# Qwiic_Hall_Effect_Sensor_TMAG5273_Mini.net
KiCad netlist of a schematic drawn in EAGLE
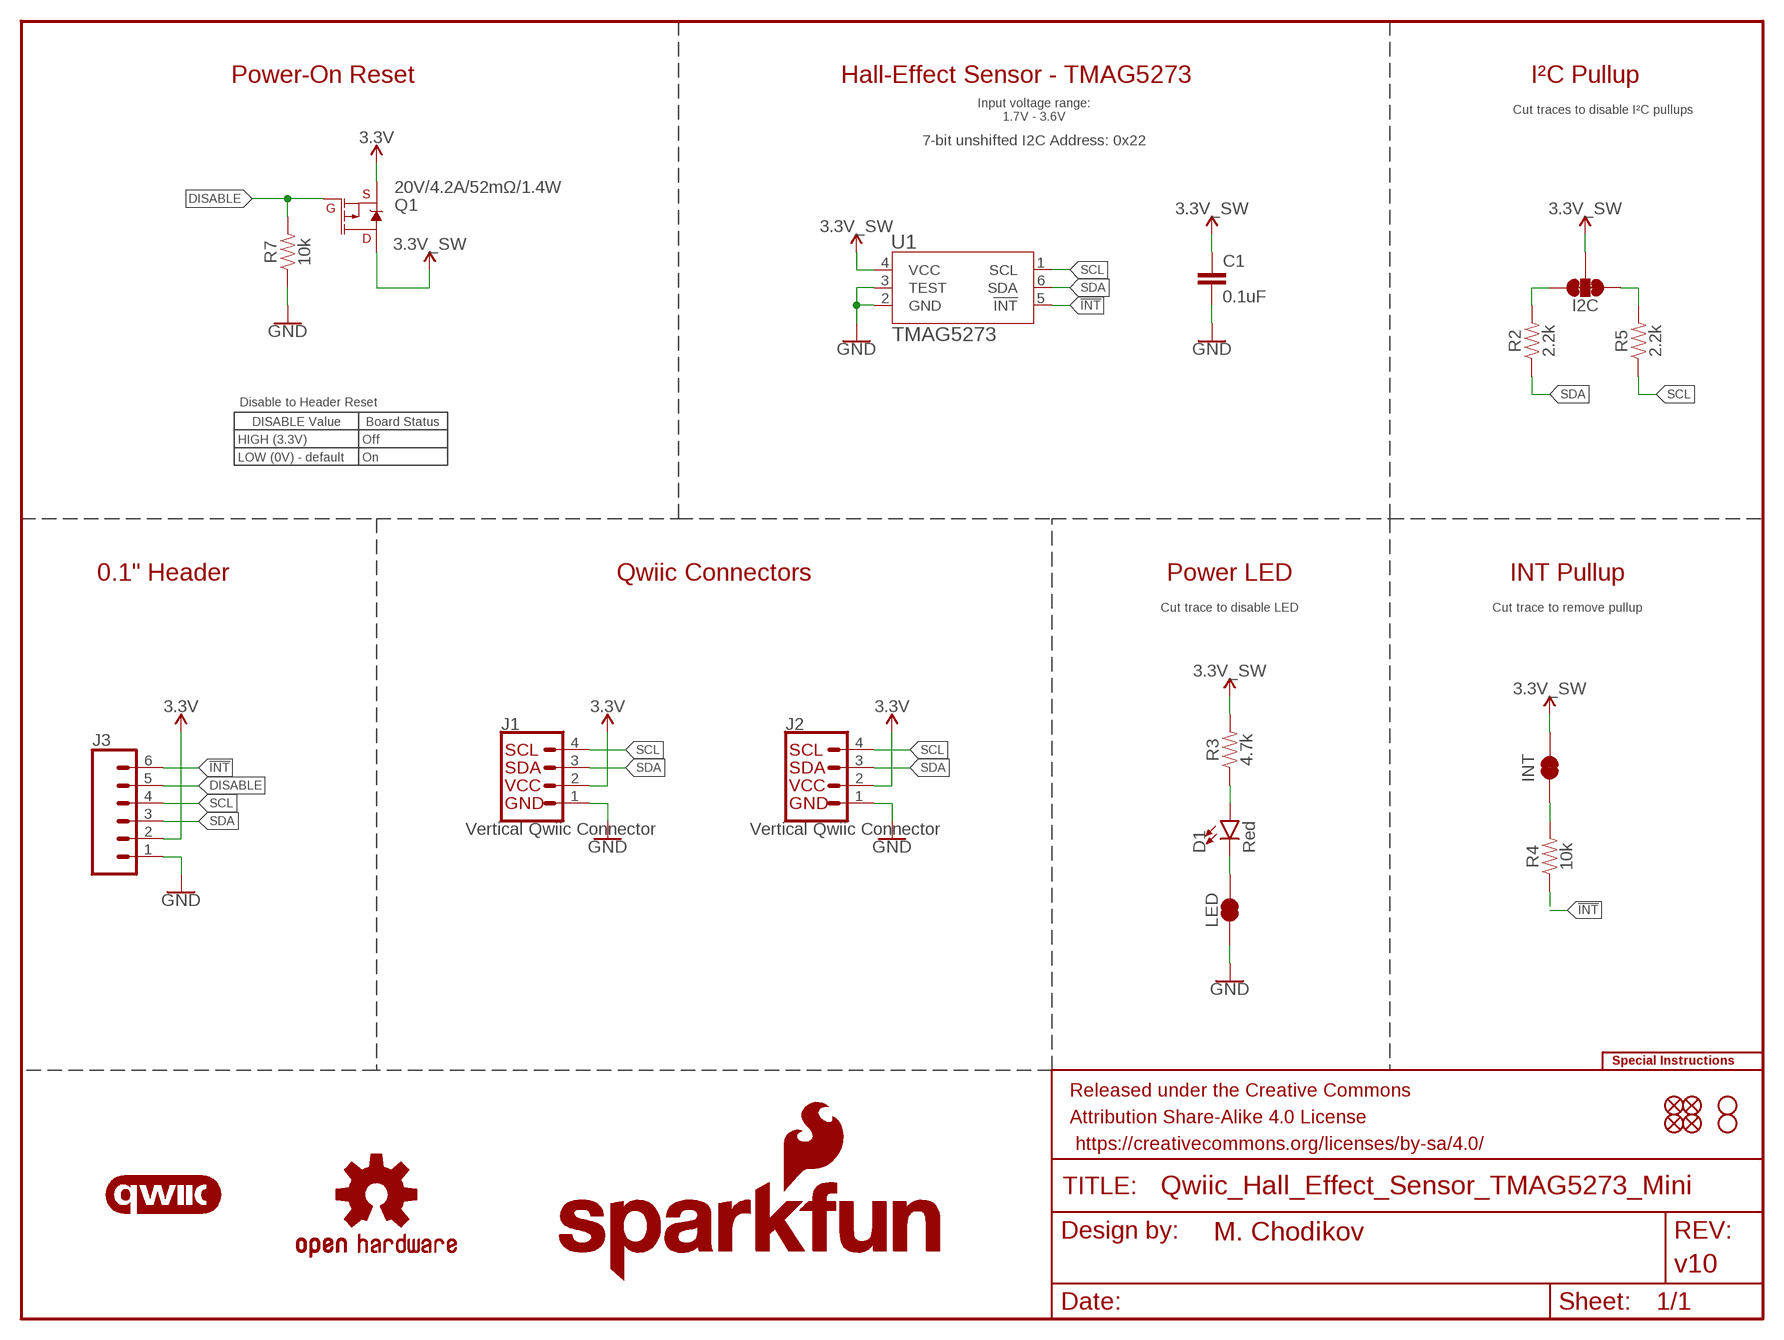
[diagram p0: schematic, sheet 1]

(export (version "E")
  (design (tool "Eeschema 10.0.6"))
  (components
    (comp (ref "C1")
      (value "0.1uF")
      (footprint "eagle-import:0603")
      (libsource (lib "eagle-import") (part "0.1UF-0603-25V-10%-X7R-WE"))
    )
    (comp (ref "D1")
      (value "Red")
      (footprint "eagle-import:LED-0603")
      (libsource (lib "eagle-import") (part "LED-RED_0603-KB"))
    )
    (comp (ref "FD1")
      (value "FIDUCIAL1X2")
      (footprint "eagle-import:FIDUCIAL-1X2")
      (libsource (lib "eagle-import") (part "FIDUCIAL1X2"))
    )
    (comp (ref "FD2")
      (value "FIDUCIAL1X2")
      (footprint "eagle-import:FIDUCIAL-1X2")
      (libsource (lib "eagle-import") (part "FIDUCIAL1X2"))
    )
    (comp (ref "FD3")
      (value "FIDUCIAL1X2")
      (footprint "eagle-import:FIDUCIAL-1X2")
      (libsource (lib "eagle-import") (part "FIDUCIAL1X2"))
    )
    (comp (ref "FD4")
      (value "FIDUCIAL1X2")
      (footprint "eagle-import:FIDUCIAL-1X2")
      (libsource (lib "eagle-import") (part "FIDUCIAL1X2"))
    )
    (comp (ref "FRAME1")
      (value "FRAME-LETTER")
      (footprint "eagle-import:CREATIVE_COMMONS")
      (fields (field (name "DESIGNER") "M. Chodikov") (field (name "REV") "v10"))
      (libsource (lib "eagle-import") (part "FRAME-LETTER"))
    )
    (comp (ref "H2")
      (value "STAND-OFF")
      (footprint "eagle-import:STAND-OFF")
      (libsource (lib "eagle-import") (part "STAND-OFF"))
    )
    (comp (ref "H4")
      (value "STAND-OFF")
      (footprint "eagle-import:STAND-OFF")
      (libsource (lib "eagle-import") (part "STAND-OFF"))
    )
    (comp (ref "I2C")
      (value "JUMPER-SMT_3_2-NC_TRACE_SILK")
      (footprint "eagle-import:SMT-JUMPER_3_2-NC_TRACE_SILK")
      (libsource (lib "eagle-import") (part "JUMPER-SMT_3_2-NC_TRACE_SILK"))
    )
    (comp (ref "INT")
      (value "JUMPER-SMT_2_NC_TRACE_SILK")
      (footprint "eagle-import:SMT-JUMPER_2_NC_TRACE_SILK")
      (libsource (lib "eagle-import") (part "JUMPER-SMT_2_NC_TRACE_SILK"))
    )
    (comp (ref "J1")
      (value "Vertical Qwiic Connector")
      (footprint "eagle-import:JST04_1MM_VERT")
      (libsource (lib "eagle-import") (part "QWIIC_CONNECTOR"))
    )
    (comp (ref "J2")
      (value "Vertical Qwiic Connector")
      (footprint "eagle-import:JST04_1MM_VERT")
      (libsource (lib "eagle-import") (part "QWIIC_CONNECTOR"))
    )
    (comp (ref "J3")
      (value "CONN_06NO_SILK_FEMALE_PTH")
      (footprint "eagle-import:1X06_NO_SILK")
      (libsource (lib "eagle-import") (part "CONN_06NO_SILK_FEMALE_PTH"))
    )
    (comp (ref "LED")
      (value "JUMPER-SMT_2_NC_TRACE_SILK")
      (footprint "eagle-import:SMT-JUMPER_2_NC_TRACE_SILK")
      (libsource (lib "eagle-import") (part "JUMPER-SMT_2_NC_TRACE_SILK"))
    )
    (comp (ref "LOGO1")
      (value "OSHW-LOGOMINI")
      (footprint "eagle-import:OSHW-LOGO-MINI")
      (libsource (lib "eagle-import") (part "OSHW-LOGOMINI"))
    )
    (comp (ref "LOGO2")
      (value "SFE_LOGO_NAME_FLAME5_MM")
      (footprint "eagle-import:SFE_LOGO_NAME_FLAME_5MM")
      (libsource (lib "eagle-import") (part "SFE_LOGO_NAME_FLAME5_MM"))
    )
    (comp (ref "LOGO3")
      (value "QWIIC_LOGO_4MM")
      (footprint "eagle-import:QWIIC_4MM")
      (libsource (lib "eagle-import") (part "QWIIC_LOGO_4MM"))
    )
    (comp (ref "LOGO4")
      (value "SFE_LOGO_NAME7_MM")
      (footprint "eagle-import:SFE_LOGO_NAME_7MM")
      (libsource (lib "eagle-import") (part "SFE_LOGO_NAME7_MM"))
    )
    (comp (ref "LOGO5")
      (value "SPECIAL_INSTRUCTIONS-ORDERING")
      (footprint "eagle-import:ORDERING_INSTRUCTIONS")
      (libsource (lib "eagle-import") (part "SPECIAL_INSTRUCTIONS-ORDERING"))
    )
    (comp (ref "LOGO6")
      (value "SFE_LOGO_FLAME.1_INCH")
      (footprint "eagle-import:SFE_LOGO_FLAME_.1")
      (libsource (lib "eagle-import") (part "SFE_LOGO_FLAME.1_INCH"))
    )
    (comp (ref "Q1")
      (value "20V/4.2A/52mΩ/1.4W")
      (footprint "eagle-import:SOT23-3")
      (libsource (lib "eagle-import") (part "MOSFET_PCH-DMG2305UX-7"))
    )
    (comp (ref "R2")
      (value "2.2k")
      (footprint "eagle-import:0603")
      (libsource (lib "eagle-import") (part "2.2KOHM-0603-1/10W-1%"))
    )
    (comp (ref "R3")
      (value "4.7k")
      (footprint "eagle-import:0603")
      (libsource (lib "eagle-import") (part "4.7KOHM-0603-1/10W-1%"))
    )
    (comp (ref "R4")
      (value "10k")
      (footprint "eagle-import:0603")
      (libsource (lib "eagle-import") (part "10KOHM-0603-1/10W-1%"))
    )
    (comp (ref "R5")
      (value "2.2k")
      (footprint "eagle-import:0603")
      (libsource (lib "eagle-import") (part "2.2KOHM-0603-1/10W-1%"))
    )
    (comp (ref "R7")
      (value "10k")
      (footprint "eagle-import:0603")
      (libsource (lib "eagle-import") (part "10KOHM-0603-1/10W-1%"))
    )
    (comp (ref "U1")
      (value "TMAG5273")
      (footprint "eagle-import:SOT23-6_DBV_TEX")
      (libsource (lib "eagle-import") (part "TMAG5273A1QDBVT"))
    )
  )
  (nets
    (net (code "1") (name "/~{INT}") (class "Default")
      (node (ref "J3") (pin "6") (pinfunction "6_6") (pintype "passive"))
      (node (ref "R4") (pin "1") (pinfunction "1_1") (pintype "passive"))
      (node (ref "U1") (pin "5") (pinfunction "~{INT}_5") (pintype "bidirectional"))
    )
    (net (code "2") (name "3.3V") (class "Default")
      (node (ref "J1") (pin "2") (pinfunction "2_2") (pintype "power_in"))
      (node (ref "J2") (pin "2") (pinfunction "2_2") (pintype "power_in"))
      (node (ref "J3") (pin "2") (pinfunction "2_2") (pintype "passive"))
      (node (ref "Q1") (pin "2") (pinfunction "S_2") (pintype "bidirectional"))
    )
    (net (code "3") (name "3.3V_SW") (class "Default")
      (node (ref "C1") (pin "1") (pinfunction "1_1") (pintype "passive"))
      (node (ref "I2C") (pin "2") (pinfunction "2_2") (pintype "passive"))
      (node (ref "INT") (pin "2") (pinfunction "2_2") (pintype "passive"))
      (node (ref "Q1") (pin "3") (pinfunction "D_3") (pintype "bidirectional"))
      (node (ref "R3") (pin "2") (pinfunction "2_2") (pintype "passive"))
      (node (ref "U1") (pin "4") (pinfunction "VCC_4") (pintype "power_in"))
    )
    (net (code "4") (name "DISABLE") (class "Default")
      (node (ref "J3") (pin "5") (pinfunction "5_5") (pintype "passive"))
      (node (ref "Q1") (pin "1") (pinfunction "G_1") (pintype "bidirectional"))
      (node (ref "R7") (pin "2") (pinfunction "2_2") (pintype "passive"))
    )
    (net (code "5") (name "GND") (class "Default")
      (node (ref "C1") (pin "2") (pinfunction "2_2") (pintype "passive"))
      (node (ref "J1") (pin "1") (pinfunction "1_1") (pintype "power_in"))
      (node (ref "J2") (pin "1") (pinfunction "1_1") (pintype "power_in"))
      (node (ref "J3") (pin "1") (pinfunction "1_1") (pintype "passive"))
      (node (ref "LED") (pin "1") (pinfunction "1_1") (pintype "passive"))
      (node (ref "R7") (pin "1") (pinfunction "1_1") (pintype "passive"))
      (node (ref "U1") (pin "2") (pinfunction "GND_2") (pintype "passive"))
      (node (ref "U1") (pin "3") (pinfunction "TEST_3") (pintype "input"))
    )
    (net (code "6") (name "Net-(D1-PadA)") (class "Default")
      (node (ref "D1") (pin "A") (pinfunction "A_A") (pintype "passive"))
      (node (ref "R3") (pin "1") (pinfunction "1_1") (pintype "passive"))
    )
    (net (code "7") (name "Net-(D1-PadC)") (class "Default")
      (node (ref "D1") (pin "C") (pinfunction "C_C") (pintype "passive"))
      (node (ref "LED") (pin "2") (pinfunction "2_2") (pintype "passive"))
    )
    (net (code "8") (name "Net-(I2C-Pad1)") (class "Default")
      (node (ref "I2C") (pin "1") (pinfunction "1_1") (pintype "passive"))
      (node (ref "R5") (pin "2") (pinfunction "2_2") (pintype "passive"))
    )
    (net (code "9") (name "Net-(I2C-Pad3)") (class "Default")
      (node (ref "I2C") (pin "3") (pinfunction "3_3") (pintype "passive"))
      (node (ref "R2") (pin "2") (pinfunction "2_2") (pintype "passive"))
    )
    (net (code "10") (name "Net-(INT-Pad1)") (class "Default")
      (node (ref "INT") (pin "1") (pinfunction "1_1") (pintype "passive"))
      (node (ref "R4") (pin "2") (pinfunction "2_2") (pintype "passive"))
    )
    (net (code "11") (name "SCL") (class "Default")
      (node (ref "J1") (pin "4") (pinfunction "4_4") (pintype "passive"))
      (node (ref "J2") (pin "4") (pinfunction "4_4") (pintype "passive"))
      (node (ref "J3") (pin "4") (pinfunction "4_4") (pintype "passive"))
      (node (ref "R5") (pin "1") (pinfunction "1_1") (pintype "passive"))
      (node (ref "U1") (pin "1") (pinfunction "SCL_1") (pintype "bidirectional"))
    )
    (net (code "12") (name "SDA") (class "Default")
      (node (ref "J1") (pin "3") (pinfunction "3_3") (pintype "passive"))
      (node (ref "J2") (pin "3") (pinfunction "3_3") (pintype "passive"))
      (node (ref "J3") (pin "3") (pinfunction "3_3") (pintype "passive"))
      (node (ref "R2") (pin "1") (pinfunction "1_1") (pintype "passive"))
      (node (ref "U1") (pin "6") (pinfunction "SDA_6") (pintype "bidirectional"))
    )
  )
)
